# demonic-cats.net
KiCad netlist of a schematic drawn in EAGLE
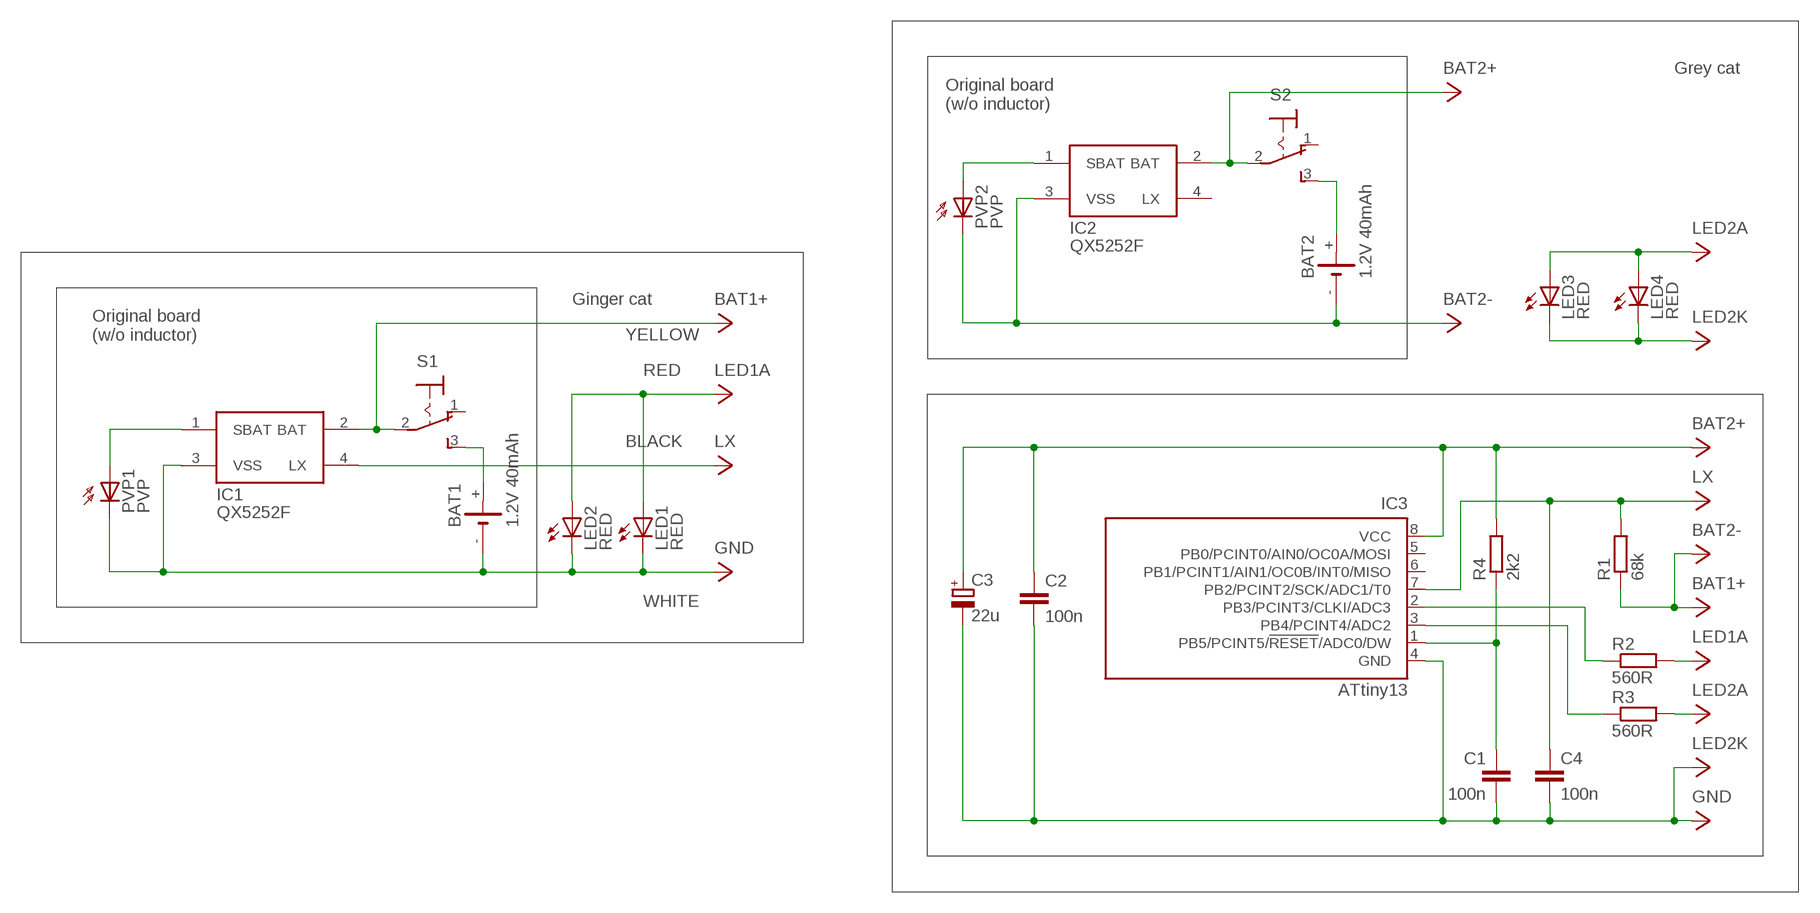
[diagram p0: schematic, sheet 1]

(export (version "E")
  (design (tool "Eeschema 10.0.6"))
  (components
    (comp (ref "BAT1")
      (value "1.2V 40mAh")
      (footprint "eagle-import:SL-150-1_2AA_PR")
      (libsource (lib "eagle-import") (part "SL-150-1/2AA/PR"))
    )
    (comp (ref "BAT2")
      (value "1.2V 40mAh")
      (footprint "eagle-import:SL-150-1_2AA_PR")
      (libsource (lib "eagle-import") (part "SL-150-1/2AA/PR"))
    )
    (comp (ref "C1")
      (value "100n")
      (footprint "eagle-import:C2.5-3")
      (libsource (lib "eagle-import") (part "C2,5-3"))
    )
    (comp (ref "C2")
      (value "100n")
      (footprint "eagle-import:C2.5-3")
      (libsource (lib "eagle-import") (part "C2,5-3"))
    )
    (comp (ref "C3")
      (value "22u")
      (footprint "eagle-import:085CS_1AR")
      (libsource (lib "eagle-import") (part "CPOL-EU085CS-1AR"))
    )
    (comp (ref "C4")
      (value "100n")
      (footprint "eagle-import:C2.5-3")
      (libsource (lib "eagle-import") (part "C2,5-3"))
    )
    (comp (ref "IC1")
      (value "QX5252F")
      (footprint "eagle-import:FAKE4")
      (libsource (lib "eagle-import") (part "QX5252"))
    )
    (comp (ref "IC2")
      (value "QX5252F")
      (footprint "eagle-import:FAKE4")
      (libsource (lib "eagle-import") (part "QX5252"))
    )
    (comp (ref "IC3")
      (value "ATtiny13")
      (footprint "eagle-import:DIL08")
      (fields (field (name "MPN") "ATTINY13-20PU"))
      (libsource (lib "eagle-import") (part "TINY13PU-20"))
    )
    (comp (ref "LED1")
      (value "RED")
      (footprint "eagle-import:W57B")
      (libsource (lib "eagle-import") (part "W57BLA"))
    )
    (comp (ref "LED2")
      (value "RED")
      (footprint "eagle-import:W57B")
      (libsource (lib "eagle-import") (part "W57BLA"))
    )
    (comp (ref "LED3")
      (value "RED")
      (footprint "eagle-import:W57B")
      (libsource (lib "eagle-import") (part "W57BLA"))
    )
    (comp (ref "LED4")
      (value "RED")
      (footprint "eagle-import:W57B")
      (libsource (lib "eagle-import") (part "W57BLA"))
    )
    (comp (ref "PVP1")
      (value "PVP")
      (footprint "eagle-import:BP104")
      (fields (field (name "MF") "VISHAY/TELEFUNKEN") (field (name "MPN") "BP104"))
      (libsource (lib "eagle-import") (part "BP104"))
    )
    (comp (ref "PVP2")
      (value "PVP")
      (footprint "eagle-import:BP104")
      (fields (field (name "MF") "VISHAY/TELEFUNKEN") (field (name "MPN") "BP104"))
      (libsource (lib "eagle-import") (part "BP104"))
    )
    (comp (ref "R1")
      (value "68k")
      (footprint "eagle-import:R0805")
      (libsource (lib "eagle-import") (part "R"))
    )
    (comp (ref "R2")
      (value "560R")
      (footprint "eagle-import:R0805")
      (libsource (lib "eagle-import") (part "R"))
    )
    (comp (ref "R3")
      (value "560R")
      (footprint "eagle-import:R0805")
      (libsource (lib "eagle-import") (part "R"))
    )
    (comp (ref "R4")
      (value "2k2")
      (footprint "eagle-import:R0805")
      (libsource (lib "eagle-import") (part "R"))
    )
    (comp (ref "S1")
      (value "320-916")
      (footprint "eagle-import:320-916")
      (libsource (lib "eagle-import") (part "320-916"))
    )
    (comp (ref "S2")
      (value "320-916")
      (footprint "eagle-import:320-916")
      (libsource (lib "eagle-import") (part "320-916"))
    )
  )
  (nets
    (net (code "1") (name "BAT1+") (class "Default")
      (node (ref "BAT1") (pin "-") (pinfunction "-_-") (pintype "passive"))
      (node (ref "BAT2") (pin "-") (pinfunction "-_-") (pintype "passive"))
      (node (ref "C1") (pin "2") (pinfunction "2_2") (pintype "passive"))
      (node (ref "C2") (pin "1") (pinfunction "1_1") (pintype "passive"))
      (node (ref "C2") (pin "2") (pinfunction "2_2") (pintype "passive"))
      (node (ref "C3") (pin "+") (pinfunction "+_+") (pintype "passive"))
      (node (ref "C3") (pin "-") (pinfunction "-_-") (pintype "passive"))
      (node (ref "C4") (pin "1") (pinfunction "1_1") (pintype "passive"))
      (node (ref "C4") (pin "2") (pinfunction "2_2") (pintype "passive"))
      (node (ref "IC1") (pin "2") (pinfunction "BAT_2") (pintype "bidirectional"))
      (node (ref "IC1") (pin "3") (pinfunction "VSS_3") (pintype "bidirectional"))
      (node (ref "IC1") (pin "4") (pinfunction "LX_4") (pintype "bidirectional"))
      (node (ref "IC2") (pin "2") (pinfunction "BAT_2") (pintype "bidirectional"))
      (node (ref "IC2") (pin "3") (pinfunction "VSS_3") (pintype "bidirectional"))
      (node (ref "IC3") (pin "4") (pinfunction "GND_4") (pintype "power_in"))
      (node (ref "IC3") (pin "7") (pinfunction "PB2/PCINT2/SCK/ADC1/T0_7") (pintype "bidirectional"))
      (node (ref "IC3") (pin "8") (pinfunction "VCC_8") (pintype "power_in"))
      (node (ref "LED1") (pin "A") (pinfunction "A_A") (pintype "passive"))
      (node (ref "LED1") (pin "C") (pinfunction "C_C") (pintype "passive"))
      (node (ref "LED1") (pin "C@1") (pinfunction "C_C@1") (pintype "passive"))
      (node (ref "LED1") (pin "C@2") (pinfunction "C_C@2") (pintype "passive"))
      (node (ref "LED1") (pin "C@3") (pinfunction "C_C@3") (pintype "passive"))
      (node (ref "LED1") (pin "C@4") (pinfunction "C_C@4") (pintype "passive"))
      (node (ref "LED1") (pin "C@5") (pinfunction "C_C@5") (pintype "passive"))
      (node (ref "LED2") (pin "A") (pinfunction "A_A") (pintype "passive"))
      (node (ref "LED2") (pin "C") (pinfunction "C_C") (pintype "passive"))
      (node (ref "LED2") (pin "C@1") (pinfunction "C_C@1") (pintype "passive"))
      (node (ref "LED2") (pin "C@2") (pinfunction "C_C@2") (pintype "passive"))
      (node (ref "LED2") (pin "C@3") (pinfunction "C_C@3") (pintype "passive"))
      (node (ref "LED2") (pin "C@4") (pinfunction "C_C@4") (pintype "passive"))
      (node (ref "LED2") (pin "C@5") (pinfunction "C_C@5") (pintype "passive"))
      (node (ref "LED3") (pin "A") (pinfunction "A_A") (pintype "passive"))
      (node (ref "LED3") (pin "C") (pinfunction "C_C") (pintype "passive"))
      (node (ref "LED3") (pin "C@1") (pinfunction "C_C@1") (pintype "passive"))
      (node (ref "LED3") (pin "C@2") (pinfunction "C_C@2") (pintype "passive"))
      (node (ref "LED3") (pin "C@3") (pinfunction "C_C@3") (pintype "passive"))
      (node (ref "LED3") (pin "C@4") (pinfunction "C_C@4") (pintype "passive"))
      (node (ref "LED3") (pin "C@5") (pinfunction "C_C@5") (pintype "passive"))
      (node (ref "LED4") (pin "A") (pinfunction "A_A") (pintype "passive"))
      (node (ref "LED4") (pin "C") (pinfunction "C_C") (pintype "passive"))
      (node (ref "LED4") (pin "C@1") (pinfunction "C_C@1") (pintype "passive"))
      (node (ref "LED4") (pin "C@2") (pinfunction "C_C@2") (pintype "passive"))
      (node (ref "LED4") (pin "C@3") (pinfunction "C_C@3") (pintype "passive"))
      (node (ref "LED4") (pin "C@4") (pinfunction "C_C@4") (pintype "passive"))
      (node (ref "LED4") (pin "C@5") (pinfunction "C_C@5") (pintype "passive"))
      (node (ref "PVP1") (pin "K") (pinfunction "C_K") (pintype "passive"))
      (node (ref "PVP2") (pin "K") (pinfunction "C_K") (pintype "passive"))
      (node (ref "R1") (pin "1") (pinfunction "1_1") (pintype "passive"))
      (node (ref "R1") (pin "2") (pinfunction "2_2") (pintype "passive"))
      (node (ref "R2") (pin "2") (pinfunction "2_2") (pintype "passive"))
      (node (ref "R3") (pin "2") (pinfunction "2_2") (pintype "passive"))
      (node (ref "R4") (pin "2") (pinfunction "2_2") (pintype "passive"))
      (node (ref "S1") (pin "2") (pinfunction "P_2") (pintype "passive"))
      (node (ref "S2") (pin "2") (pinfunction "P_2") (pintype "passive"))
    )
    (net (code "2") (name "Net-(IC1-SBAT)") (class "Default")
      (node (ref "IC1") (pin "1") (pinfunction "SBAT_1") (pintype "bidirectional"))
      (node (ref "PVP1") (pin "A") (pinfunction "A_A") (pintype "passive"))
    )
    (net (code "3") (name "Net-(IC2-SBAT)") (class "Default")
      (node (ref "IC2") (pin "1") (pinfunction "SBAT_1") (pintype "bidirectional"))
      (node (ref "PVP2") (pin "A") (pinfunction "A_A") (pintype "passive"))
    )
    (net (code "4") (name "Net-(IC3-PB3{slash}PCINT3{slash}CLKI{slash}ADC3)") (class "Default")
      (node (ref "IC3") (pin "2") (pinfunction "PB3/PCINT3/CLKI/ADC3_2") (pintype "bidirectional"))
      (node (ref "R2") (pin "1") (pinfunction "1_1") (pintype "passive"))
    )
    (net (code "5") (name "Net-(IC3-PB4{slash}PCINT4{slash}ADC2)") (class "Default")
      (node (ref "IC3") (pin "3") (pinfunction "PB4/PCINT4/ADC2_3") (pintype "bidirectional"))
      (node (ref "R3") (pin "1") (pinfunction "1_1") (pintype "passive"))
    )
    (net (code "6") (name "Net-(IC3-PB5{slash}PCINT5{slash}~{RESET}{slash}ADC0{slash}DW)") (class "Default")
      (node (ref "C1") (pin "1") (pinfunction "1_1") (pintype "passive"))
      (node (ref "IC3") (pin "1") (pinfunction "PB5/PCINT5/~{RESET}/ADC0/DW_1") (pintype "bidirectional"))
      (node (ref "R4") (pin "1") (pinfunction "1_1") (pintype "passive"))
    )
    (net (code "7") (name "Net-(S1-S)") (class "Default")
      (node (ref "BAT1") (pin "+") (pinfunction "+_+") (pintype "passive"))
      (node (ref "S1") (pin "3") (pinfunction "S_3") (pintype "passive"))
    )
    (net (code "8") (name "Net-(S2-S)") (class "Default")
      (node (ref "BAT2") (pin "+") (pinfunction "+_+") (pintype "passive"))
      (node (ref "S2") (pin "3") (pinfunction "S_3") (pintype "passive"))
    )
    (net (code "9") (name "unconnected-(IC2-LX-Pad4)") (class "Default")
      (node (ref "IC2") (pin "4") (pinfunction "LX_4") (pintype "bidirectional"))
    )
    (net (code "10") (name "unconnected-(IC3-PB0{slash}PCINT0{slash}AIN0{slash}OC0A{slash}MOSI-Pad5)") (class "Default")
      (node (ref "IC3") (pin "5") (pinfunction "PB0/PCINT0/AIN0/OC0A/MOSI_5") (pintype "bidirectional"))
    )
    (net (code "11") (name "unconnected-(IC3-PB1{slash}PCINT1{slash}AIN1{slash}OC0B{slash}INT0{slash}MISO-Pad6)") (class "Default")
      (node (ref "IC3") (pin "6") (pinfunction "PB1/PCINT1/AIN1/OC0B/INT0/MISO_6") (pintype "bidirectional"))
    )
    (net (code "12") (name "unconnected-(S1-O-Pad1)") (class "Default")
      (node (ref "S1") (pin "1") (pinfunction "O_1") (pintype "passive"))
    )
    (net (code "13") (name "unconnected-(S2-O-Pad1)") (class "Default")
      (node (ref "S2") (pin "1") (pinfunction "O_1") (pintype "passive"))
    )
  )
)
